# STM_board.net
KiCad netlist of a schematic drawn in Altium Designer
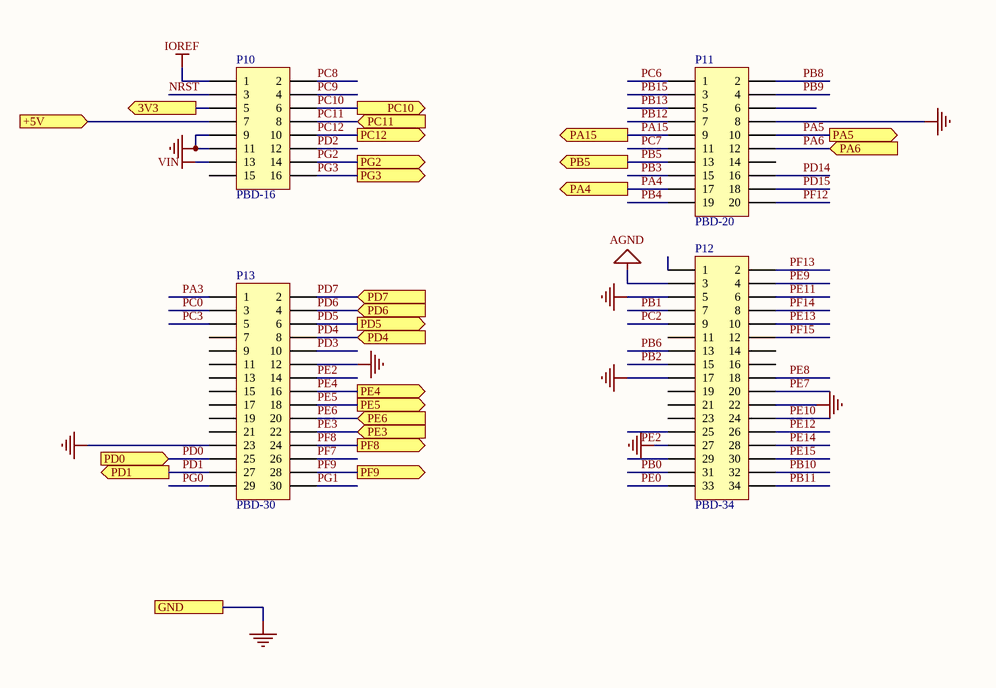
[diagram p0: STM_board.SchDoc]

(export (version "E")
  (design (tool "Eeschema 10.0.6"))
  (components
    (comp (ref "P10")
      (value "PBD-16")
      (footprint "PBD-16")
      (description "Гнездо на плату")
      (libsource (lib "db") (part "PBD-16"))
    )
    (comp (ref "P11")
      (value "PBD-20")
      (footprint "PBD-20")
      (description "Гнездо на плату")
      (libsource (lib "db") (part "PBD-20"))
    )
    (comp (ref "P12")
      (value "PBD-34")
      (footprint "PBD-34")
      (description "Гнездо на плату")
      (libsource (lib "db") (part "PBD-34"))
    )
    (comp (ref "P13")
      (value "PBD-30")
      (footprint "PBD-30")
      (description "Гнездо на плату")
      (libsource (lib "db") (part "PBD-30"))
    )
  )
  (nets
    (net (code "1") (name "/+5V") (class "Default")
      (node (ref "P10") (pin "7") (pinfunction "7_7") (pintype "passive"))
    )
    (net (code "2") (name "/3V3") (class "Default")
      (node (ref "P10") (pin "5") (pinfunction "5_5") (pintype "passive"))
    )
    (net (code "3") (name "/NRST") (class "Default")
      (node (ref "P10") (pin "3") (pinfunction "3_3") (pintype "passive"))
    )
    (net (code "4") (name "/PA3") (class "Default")
      (node (ref "P13") (pin "1") (pinfunction "1_1") (pintype "passive"))
    )
    (net (code "5") (name "/PA4") (class "Default")
      (node (ref "P11") (pin "17") (pinfunction "17_17") (pintype "passive"))
    )
    (net (code "6") (name "/PA5") (class "Default")
      (node (ref "P11") (pin "10") (pinfunction "10_10") (pintype "passive"))
    )
    (net (code "7") (name "/PA6") (class "Default")
      (node (ref "P11") (pin "12") (pinfunction "12_12") (pintype "passive"))
    )
    (net (code "8") (name "/PA15") (class "Default")
      (node (ref "P11") (pin "9") (pinfunction "9_9") (pintype "passive"))
    )
    (net (code "9") (name "/PB0") (class "Default")
      (node (ref "P12") (pin "31") (pinfunction "31_31") (pintype "passive"))
    )
    (net (code "10") (name "/PB1") (class "Default")
      (node (ref "P12") (pin "7") (pinfunction "7_7") (pintype "passive"))
    )
    (net (code "11") (name "/PB2") (class "Default")
      (node (ref "P12") (pin "15") (pinfunction "15_15") (pintype "passive"))
    )
    (net (code "12") (name "/PB3") (class "Default")
      (node (ref "P11") (pin "15") (pinfunction "15_15") (pintype "passive"))
    )
    (net (code "13") (name "/PB4") (class "Default")
      (node (ref "P11") (pin "19") (pinfunction "19_19") (pintype "passive"))
    )
    (net (code "14") (name "/PB5") (class "Default")
      (node (ref "P11") (pin "13") (pinfunction "13_13") (pintype "passive"))
    )
    (net (code "15") (name "/PB6") (class "Default")
      (node (ref "P12") (pin "13") (pinfunction "13_13") (pintype "passive"))
    )
    (net (code "16") (name "/PB8") (class "Default")
      (node (ref "P11") (pin "2") (pinfunction "2_2") (pintype "passive"))
    )
    (net (code "17") (name "/PB9") (class "Default")
      (node (ref "P11") (pin "4") (pinfunction "4_4") (pintype "passive"))
    )
    (net (code "18") (name "/PB10") (class "Default")
      (node (ref "P12") (pin "32") (pinfunction "32_32") (pintype "passive"))
    )
    (net (code "19") (name "/PB11") (class "Default")
      (node (ref "P12") (pin "34") (pinfunction "34_34") (pintype "passive"))
    )
    (net (code "20") (name "/PB12") (class "Default")
      (node (ref "P11") (pin "7") (pinfunction "7_7") (pintype "passive"))
    )
    (net (code "21") (name "/PB13") (class "Default")
      (node (ref "P11") (pin "5") (pinfunction "5_5") (pintype "passive"))
    )
    (net (code "22") (name "/PB15") (class "Default")
      (node (ref "P11") (pin "3") (pinfunction "3_3") (pintype "passive"))
    )
    (net (code "23") (name "/PC0") (class "Default")
      (node (ref "P13") (pin "3") (pinfunction "3_3") (pintype "passive"))
    )
    (net (code "24") (name "/PC2") (class "Default")
      (node (ref "P12") (pin "9") (pinfunction "9_9") (pintype "passive"))
    )
    (net (code "25") (name "/PC3") (class "Default")
      (node (ref "P13") (pin "5") (pinfunction "5_5") (pintype "passive"))
    )
    (net (code "26") (name "/PC6") (class "Default")
      (node (ref "P11") (pin "1") (pinfunction "1_1") (pintype "passive"))
    )
    (net (code "27") (name "/PC7") (class "Default")
      (node (ref "P11") (pin "11") (pinfunction "11_11") (pintype "passive"))
    )
    (net (code "28") (name "/PC8") (class "Default")
      (node (ref "P10") (pin "2") (pinfunction "2_2") (pintype "passive"))
    )
    (net (code "29") (name "/PC9") (class "Default")
      (node (ref "P10") (pin "4") (pinfunction "4_4") (pintype "passive"))
    )
    (net (code "30") (name "/PC10") (class "Default")
      (node (ref "P10") (pin "6") (pinfunction "6_6") (pintype "passive"))
    )
    (net (code "31") (name "/PC11") (class "Default")
      (node (ref "P10") (pin "8") (pinfunction "8_8") (pintype "passive"))
    )
    (net (code "32") (name "/PC12") (class "Default")
      (node (ref "P10") (pin "10") (pinfunction "10_10") (pintype "passive"))
    )
    (net (code "33") (name "/PD0") (class "Default")
      (node (ref "P13") (pin "25") (pinfunction "25_25") (pintype "passive"))
    )
    (net (code "34") (name "/PD1") (class "Default")
      (node (ref "P13") (pin "27") (pinfunction "27_27") (pintype "passive"))
    )
    (net (code "35") (name "/PD2") (class "Default")
      (node (ref "P10") (pin "12") (pinfunction "12_12") (pintype "passive"))
    )
    (net (code "36") (name "/PD3") (class "Default")
      (node (ref "P13") (pin "10") (pinfunction "10_10") (pintype "passive"))
    )
    (net (code "37") (name "/PD4") (class "Default")
      (node (ref "P13") (pin "8") (pinfunction "8_8") (pintype "passive"))
    )
    (net (code "38") (name "/PD5") (class "Default")
      (node (ref "P13") (pin "6") (pinfunction "6_6") (pintype "passive"))
    )
    (net (code "39") (name "/PD6") (class "Default")
      (node (ref "P13") (pin "4") (pinfunction "4_4") (pintype "passive"))
    )
    (net (code "40") (name "/PD7") (class "Default")
      (node (ref "P13") (pin "2") (pinfunction "2_2") (pintype "passive"))
    )
    (net (code "41") (name "/PD14") (class "Default")
      (node (ref "P11") (pin "16") (pinfunction "16_16") (pintype "passive"))
    )
    (net (code "42") (name "/PD15") (class "Default")
      (node (ref "P11") (pin "18") (pinfunction "18_18") (pintype "passive"))
    )
    (net (code "43") (name "/PE0") (class "Default")
      (node (ref "P12") (pin "33") (pinfunction "33_33") (pintype "passive"))
    )
    (net (code "44") (name "/PE2") (class "Default")
      (node (ref "P13") (pin "14") (pinfunction "14_14") (pintype "passive"))
    )
    (net (code "45") (name "/PE3") (class "Default")
      (node (ref "P13") (pin "22") (pinfunction "22_22") (pintype "passive"))
    )
    (net (code "46") (name "/PE4") (class "Default")
      (node (ref "P13") (pin "16") (pinfunction "16_16") (pintype "passive"))
    )
    (net (code "47") (name "/PE5") (class "Default")
      (node (ref "P13") (pin "18") (pinfunction "18_18") (pintype "passive"))
    )
    (net (code "48") (name "/PE6") (class "Default")
      (node (ref "P13") (pin "20") (pinfunction "20_20") (pintype "passive"))
    )
    (net (code "49") (name "/PE7") (class "Default")
      (node (ref "P12") (pin "20") (pinfunction "20_20") (pintype "passive"))
    )
    (net (code "50") (name "/PE8") (class "Default")
      (node (ref "P12") (pin "18") (pinfunction "18_18") (pintype "passive"))
    )
    (net (code "51") (name "/PE9") (class "Default")
      (node (ref "P12") (pin "4") (pinfunction "4_4") (pintype "passive"))
    )
    (net (code "52") (name "/PE10") (class "Default")
      (node (ref "P12") (pin "24") (pinfunction "24_24") (pintype "passive"))
    )
    (net (code "53") (name "/PE11") (class "Default")
      (node (ref "P12") (pin "6") (pinfunction "6_6") (pintype "passive"))
    )
    (net (code "54") (name "/PE12") (class "Default")
      (node (ref "P12") (pin "26") (pinfunction "26_26") (pintype "passive"))
    )
    (net (code "55") (name "/PE13") (class "Default")
      (node (ref "P12") (pin "10") (pinfunction "10_10") (pintype "passive"))
    )
    (net (code "56") (name "/PE14") (class "Default")
      (node (ref "P12") (pin "28") (pinfunction "28_28") (pintype "passive"))
    )
    (net (code "57") (name "/PE15") (class "Default")
      (node (ref "P12") (pin "30") (pinfunction "30_30") (pintype "passive"))
    )
    (net (code "58") (name "/PF7") (class "Default")
      (node (ref "P13") (pin "26") (pinfunction "26_26") (pintype "passive"))
    )
    (net (code "59") (name "/PF8") (class "Default")
      (node (ref "P13") (pin "24") (pinfunction "24_24") (pintype "passive"))
    )
    (net (code "60") (name "/PF9") (class "Default")
      (node (ref "P13") (pin "28") (pinfunction "28_28") (pintype "passive"))
    )
    (net (code "61") (name "/PF12") (class "Default")
      (node (ref "P11") (pin "20") (pinfunction "20_20") (pintype "passive"))
    )
    (net (code "62") (name "/PF13") (class "Default")
      (node (ref "P12") (pin "2") (pinfunction "2_2") (pintype "passive"))
    )
    (net (code "63") (name "/PF14") (class "Default")
      (node (ref "P12") (pin "8") (pinfunction "8_8") (pintype "passive"))
    )
    (net (code "64") (name "/PF15") (class "Default")
      (node (ref "P12") (pin "12") (pinfunction "12_12") (pintype "passive"))
    )
    (net (code "65") (name "/PG0") (class "Default")
      (node (ref "P13") (pin "29") (pinfunction "29_29") (pintype "passive"))
    )
    (net (code "66") (name "/PG1") (class "Default")
      (node (ref "P13") (pin "30") (pinfunction "30_30") (pintype "passive"))
    )
    (net (code "67") (name "/PG2") (class "Default")
      (node (ref "P10") (pin "14") (pinfunction "14_14") (pintype "passive"))
    )
    (net (code "68") (name "/PG3") (class "Default")
      (node (ref "P10") (pin "16") (pinfunction "16_16") (pintype "passive"))
    )
    (net (code "69") (name "AGND") (class "Default")
      (node (ref "P12") (pin "3") (pinfunction "3_3") (pintype "passive"))
    )
    (net (code "70") (name "GND") (class "Default")
      (node (ref "P10") (pin "11") (pinfunction "11_11") (pintype "passive"))
      (node (ref "P10") (pin "9") (pinfunction "9_9") (pintype "passive"))
      (node (ref "P11") (pin "8") (pinfunction "8_8") (pintype "passive"))
      (node (ref "P12") (pin "17") (pinfunction "17_17") (pintype "passive"))
      (node (ref "P12") (pin "22") (pinfunction "22_22") (pintype "passive"))
      (node (ref "P12") (pin "27") (pinfunction "27_27") (pintype "passive"))
      (node (ref "P12") (pin "5") (pinfunction "5_5") (pintype "passive"))
      (node (ref "P13") (pin "12") (pinfunction "12_12") (pintype "passive"))
      (node (ref "P13") (pin "23") (pinfunction "23_23") (pintype "passive"))
    )
    (net (code "71") (name "IOREF") (class "Default")
      (node (ref "P10") (pin "1") (pinfunction "1_1") (pintype "passive"))
    )
    (net (code "72") (name "VIN") (class "Default")
      (node (ref "P10") (pin "13") (pinfunction "13_13") (pintype "passive"))
    )
    (net (code "73") (name "unconnected-(P10-Pad15)") (class "Default")
      (node (ref "P10") (pin "15") (pinfunction "15_15") (pintype "passive"))
    )
    (net (code "74") (name "unconnected-(P11-Pad6)") (class "Default")
      (node (ref "P11") (pin "6") (pinfunction "6_6") (pintype "passive"))
    )
    (net (code "75") (name "unconnected-(P11-Pad14)") (class "Default")
      (node (ref "P11") (pin "14") (pinfunction "14_14") (pintype "passive"))
    )
    (net (code "76") (name "unconnected-(P12-Pad1)") (class "Default")
      (node (ref "P12") (pin "1") (pinfunction "1_1") (pintype "passive"))
    )
    (net (code "77") (name "unconnected-(P12-Pad11)") (class "Default")
      (node (ref "P12") (pin "11") (pinfunction "11_11") (pintype "passive"))
    )
    (net (code "78") (name "unconnected-(P12-Pad14)") (class "Default")
      (node (ref "P12") (pin "14") (pinfunction "14_14") (pintype "passive"))
    )
    (net (code "79") (name "unconnected-(P12-Pad16)") (class "Default")
      (node (ref "P12") (pin "16") (pinfunction "16_16") (pintype "passive"))
    )
    (net (code "80") (name "unconnected-(P12-Pad19)") (class "Default")
      (node (ref "P12") (pin "19") (pinfunction "19_19") (pintype "passive"))
    )
    (net (code "81") (name "unconnected-(P12-Pad21)") (class "Default")
      (node (ref "P12") (pin "21") (pinfunction "21_21") (pintype "passive"))
    )
    (net (code "82") (name "unconnected-(P12-Pad23)") (class "Default")
      (node (ref "P12") (pin "23") (pinfunction "23_23") (pintype "passive"))
    )
    (net (code "83") (name "unconnected-(P12-Pad25)") (class "Default")
      (node (ref "P12") (pin "25") (pinfunction "25_25") (pintype "passive"))
    )
    (net (code "84") (name "unconnected-(P12-Pad29)") (class "Default")
      (node (ref "P12") (pin "29") (pinfunction "29_29") (pintype "passive"))
    )
    (net (code "85") (name "unconnected-(P13-Pad7)") (class "Default")
      (node (ref "P13") (pin "7") (pinfunction "7_7") (pintype "passive"))
    )
    (net (code "86") (name "unconnected-(P13-Pad9)") (class "Default")
      (node (ref "P13") (pin "9") (pinfunction "9_9") (pintype "passive"))
    )
    (net (code "87") (name "unconnected-(P13-Pad11)") (class "Default")
      (node (ref "P13") (pin "11") (pinfunction "11_11") (pintype "passive"))
    )
    (net (code "88") (name "unconnected-(P13-Pad13)") (class "Default")
      (node (ref "P13") (pin "13") (pinfunction "13_13") (pintype "passive"))
    )
    (net (code "89") (name "unconnected-(P13-Pad15)") (class "Default")
      (node (ref "P13") (pin "15") (pinfunction "15_15") (pintype "passive"))
    )
    (net (code "90") (name "unconnected-(P13-Pad17)") (class "Default")
      (node (ref "P13") (pin "17") (pinfunction "17_17") (pintype "passive"))
    )
    (net (code "91") (name "unconnected-(P13-Pad19)") (class "Default")
      (node (ref "P13") (pin "19") (pinfunction "19_19") (pintype "passive"))
    )
    (net (code "92") (name "unconnected-(P13-Pad21)") (class "Default")
      (node (ref "P13") (pin "21") (pinfunction "21_21") (pintype "passive"))
    )
  )
)
